# ControllerBoard.net
KiCad netlist of a schematic drawn in EAGLE
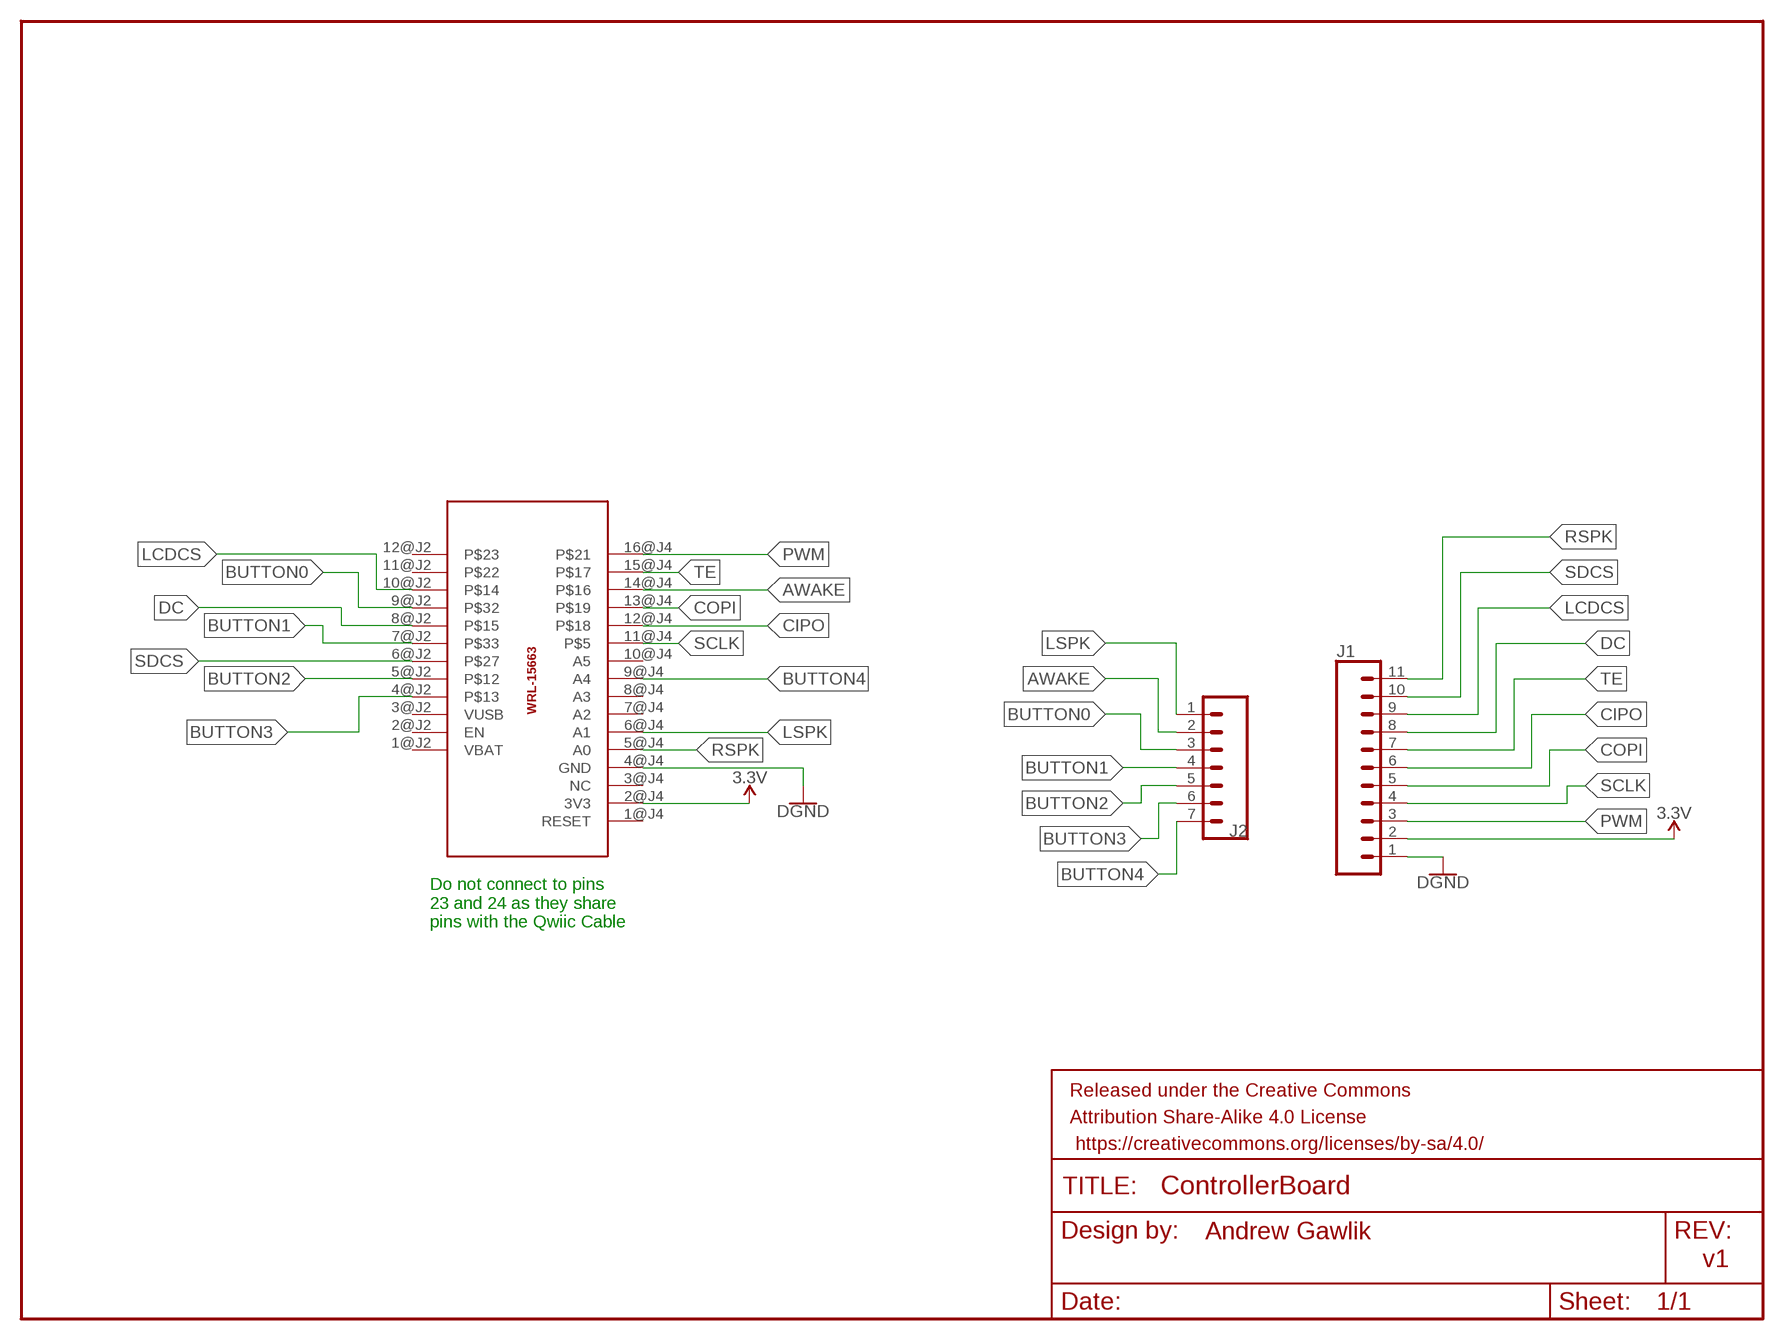
[diagram p0: schematic, sheet 1]

(export (version "E")
  (design (tool "Eeschema 10.0.6"))
  (components
    (comp (ref "A1")
      (value "ESP32_MICROCONTROLLER")
      (footprint "eagle-import:WRL-17381")
      (libsource (lib "eagle-import") (part "WRL-17381"))
    )
    (comp (ref "FRAME1")
      (value "FRAME-LETTER")
      (footprint "eagle-import:CREATIVE_COMMONS")
      (libsource (lib "eagle-import") (part "FRAME-LETTER"))
    )
    (comp (ref "J1")
      (value "CONN_11LOCK")
      (footprint "eagle-import:1X11_LOCK")
      (libsource (lib "eagle-import") (part "CONN_11LOCK"))
    )
    (comp (ref "J2")
      (value "CONN_07LOCK")
      (footprint "eagle-import:1X07_LOCK")
      (libsource (lib "eagle-import") (part "CONN_07LOCK"))
    )
  )
  (nets
    (net (code "1") (name "3.3V") (class "Default")
      (node (ref "A1") (pin "2@J4") (pinfunction "3V3_2@J4") (pintype "power_in"))
      (node (ref "J1") (pin "2") (pinfunction "2_2") (pintype "passive"))
    )
    (net (code "2") (name "AWAKE") (class "Default")
      (node (ref "A1") (pin "14@J4") (pinfunction "P$16_14@J4") (pintype "bidirectional"))
      (node (ref "J2") (pin "2") (pinfunction "2_2") (pintype "passive"))
    )
    (net (code "3") (name "BUTTON0") (class "Default")
      (node (ref "A1") (pin "9@J2") (pinfunction "P$32_9@J2") (pintype "bidirectional"))
      (node (ref "J2") (pin "3") (pinfunction "3_3") (pintype "passive"))
    )
    (net (code "4") (name "BUTTON1") (class "Default")
      (node (ref "A1") (pin "7@J2") (pinfunction "P$33_7@J2") (pintype "bidirectional"))
      (node (ref "J2") (pin "4") (pinfunction "4_4") (pintype "passive"))
    )
    (net (code "5") (name "BUTTON2") (class "Default")
      (node (ref "A1") (pin "5@J2") (pinfunction "P$12_5@J2") (pintype "bidirectional"))
      (node (ref "J2") (pin "5") (pinfunction "5_5") (pintype "passive"))
    )
    (net (code "6") (name "BUTTON3") (class "Default")
      (node (ref "A1") (pin "4@J2") (pinfunction "P$13_4@J2") (pintype "bidirectional"))
      (node (ref "J2") (pin "6") (pinfunction "6_6") (pintype "passive"))
    )
    (net (code "7") (name "BUTTON4") (class "Default")
      (node (ref "A1") (pin "9@J4") (pinfunction "A4_9@J4") (pintype "bidirectional"))
      (node (ref "J2") (pin "7") (pinfunction "7_7") (pintype "passive"))
    )
    (net (code "8") (name "CIPO") (class "Default")
      (node (ref "A1") (pin "12@J4") (pinfunction "P$18_12@J4") (pintype "bidirectional"))
      (node (ref "J1") (pin "6") (pinfunction "6_6") (pintype "passive"))
    )
    (net (code "9") (name "COPI") (class "Default")
      (node (ref "A1") (pin "13@J4") (pinfunction "P$19_13@J4") (pintype "bidirectional"))
      (node (ref "J1") (pin "5") (pinfunction "5_5") (pintype "passive"))
    )
    (net (code "10") (name "DC") (class "Default")
      (node (ref "A1") (pin "8@J2") (pinfunction "P$15_8@J2") (pintype "bidirectional"))
      (node (ref "J1") (pin "8") (pinfunction "8_8") (pintype "passive"))
    )
    (net (code "11") (name "DGND") (class "Default")
      (node (ref "A1") (pin "4@J4") (pinfunction "GND_4@J4") (pintype "power_in"))
      (node (ref "J1") (pin "1") (pinfunction "1_1") (pintype "passive"))
    )
    (net (code "12") (name "LCDCS") (class "Default")
      (node (ref "A1") (pin "10@J2") (pinfunction "P$14_10@J2") (pintype "bidirectional"))
      (node (ref "J1") (pin "9") (pinfunction "9_9") (pintype "passive"))
    )
    (net (code "13") (name "LSPK") (class "Default")
      (node (ref "A1") (pin "6@J4") (pinfunction "A1_6@J4") (pintype "bidirectional"))
      (node (ref "J2") (pin "1") (pinfunction "1_1") (pintype "passive"))
    )
    (net (code "14") (name "PWM") (class "Default")
      (node (ref "A1") (pin "16@J4") (pinfunction "P$21_16@J4") (pintype "bidirectional"))
      (node (ref "J1") (pin "3") (pinfunction "3_3") (pintype "passive"))
    )
    (net (code "15") (name "RSPK") (class "Default")
      (node (ref "A1") (pin "5@J4") (pinfunction "A0_5@J4") (pintype "bidirectional"))
      (node (ref "J1") (pin "11") (pinfunction "11_11") (pintype "passive"))
    )
    (net (code "16") (name "SCLK") (class "Default")
      (node (ref "A1") (pin "11@J4") (pinfunction "P$5_11@J4") (pintype "bidirectional"))
      (node (ref "J1") (pin "4") (pinfunction "4_4") (pintype "passive"))
    )
    (net (code "17") (name "SDCS") (class "Default")
      (node (ref "A1") (pin "6@J2") (pinfunction "P$27_6@J2") (pintype "bidirectional"))
      (node (ref "J1") (pin "10") (pinfunction "10_10") (pintype "passive"))
    )
    (net (code "18") (name "TE") (class "Default")
      (node (ref "A1") (pin "15@J4") (pinfunction "P$17_15@J4") (pintype "bidirectional"))
      (node (ref "J1") (pin "7") (pinfunction "7_7") (pintype "passive"))
    )
    (net (code "19") (name "unconnected-(A1-A2-Pad7@J4)") (class "Default")
      (node (ref "A1") (pin "7@J4") (pinfunction "A2_7@J4") (pintype "bidirectional"))
    )
    (net (code "20") (name "unconnected-(A1-A3-Pad8@J4)") (class "Default")
      (node (ref "A1") (pin "8@J4") (pinfunction "A3_8@J4") (pintype "bidirectional"))
    )
    (net (code "21") (name "unconnected-(A1-A5-Pad10@J4)") (class "Default")
      (node (ref "A1") (pin "10@J4") (pinfunction "A5_10@J4") (pintype "bidirectional"))
    )
    (net (code "22") (name "unconnected-(A1-EN-Pad2@J2)") (class "Default")
      (node (ref "A1") (pin "2@J2") (pinfunction "EN_2@J2") (pintype "output"))
    )
    (net (code "23") (name "unconnected-(A1-NC-Pad3@J4)") (class "Default")
      (node (ref "A1") (pin "3@J4") (pinfunction "NC_3@J4") (pintype "no_connect"))
    )
    (net (code "24") (name "unconnected-(A1-P$22-Pad11@J2)") (class "Default")
      (node (ref "A1") (pin "11@J2") (pinfunction "P$22_11@J2") (pintype "bidirectional"))
    )
    (net (code "25") (name "unconnected-(A1-P$23-Pad12@J2)") (class "Default")
      (node (ref "A1") (pin "12@J2") (pinfunction "P$23_12@J2") (pintype "bidirectional"))
    )
    (net (code "26") (name "unconnected-(A1-RESET-Pad1@J4)") (class "Default")
      (node (ref "A1") (pin "1@J4") (pinfunction "RESET_1@J4") (pintype "bidirectional"))
    )
    (net (code "27") (name "unconnected-(A1-VBAT-Pad1@J2)") (class "Default")
      (node (ref "A1") (pin "1@J2") (pinfunction "VBAT_1@J2") (pintype "no_connect"))
    )
    (net (code "28") (name "unconnected-(A1-VUSB-Pad3@J2)") (class "Default")
      (node (ref "A1") (pin "3@J2") (pinfunction "VUSB_3@J2") (pintype "no_connect"))
    )
  )
)
